# TLS_PWR.net
KiCad netlist of a schematic drawn in Altium Designer
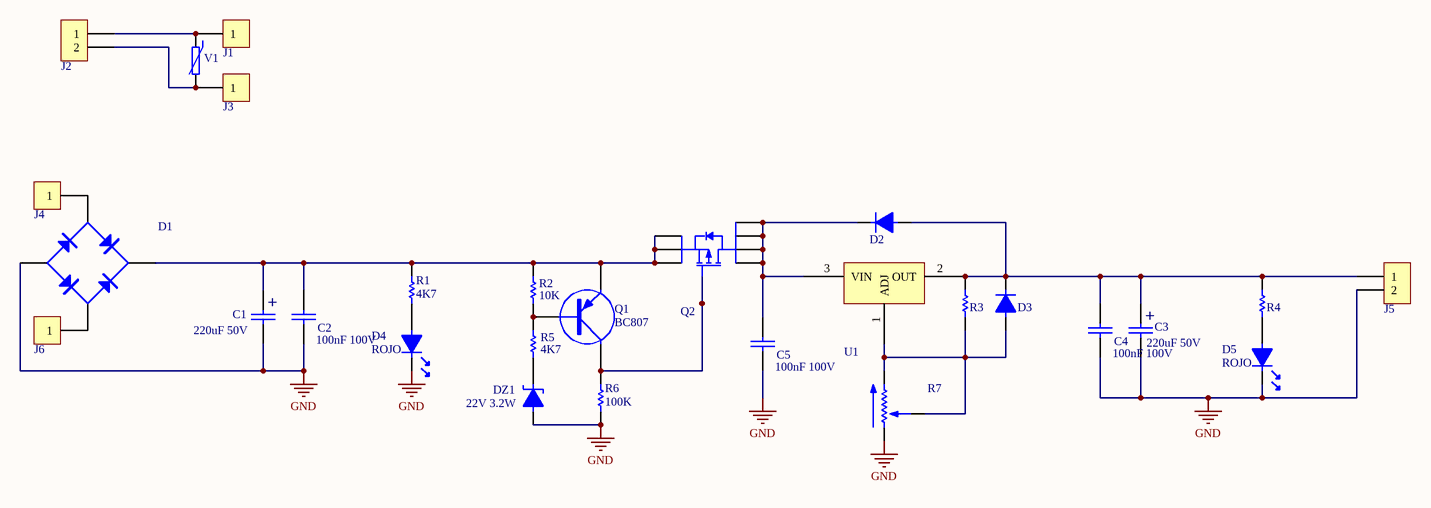
[diagram p0: TLS_PWR.SchDoc]

(export (version "E")
  (design (tool "Eeschema 10.0.6"))
  (components
    (comp (ref "C1")
      (value "220uF 50V")
      (footprint "CAP500RP")
      (description "CAP ELECT 220uF 50V")
      (fields (field (name "PART NUMBER") "CAP_ELECT_220uF_50V") (field (name "MANUFACTURER") "Nichicon"))
      (libsource (lib "gl_LIB") (part "CAPPOL"))
    )
    (comp (ref "C2")
      (value "100nF 100V")
      (footprint "0603")
      (description "CAP0603 100nF 100V X7R")
      (fields (field (name "PART NUMBER") "CAP0603_100nF_100V_X7R") (field (name "MANUFACTURER") "Yageo"))
      (libsource (lib "gl_LIB") (part "CAP"))
    )
    (comp (ref "C3")
      (value "220uF 50V")
      (footprint "CAP500RP")
      (description "CAP ELECT 220uF 50V")
      (fields (field (name "PART NUMBER") "CAP_ELECT_220uF_50V") (field (name "MANUFACTURER") "Nichicon"))
      (libsource (lib "gl_LIB") (part "CAPPOL"))
    )
    (comp (ref "C4")
      (value "100nF 100V")
      (footprint "0603")
      (description "CAP0603 100nF 100V X7R")
      (fields (field (name "PART NUMBER") "CAP0603_100nF_100V_X7R") (field (name "MANUFACTURER") "Yageo"))
      (libsource (lib "gl_LIB") (part "CAP"))
    )
    (comp (ref "C5")
      (value "100nF 100V")
      (footprint "0603")
      (description "CAP0603 100nF 100V X7R")
      (fields (field (name "PART NUMBER") "CAP0603_100nF_100V_X7R") (field (name "MANUFACTURER") "Yageo"))
      (libsource (lib "gl_LIB") (part "CAP"))
    )
    (comp (ref "D1")
      (value "CD-MBL210S")
      (footprint "CD-MBL210S")
      (description "BRIDGE RECT 1PHASE 1KV 2A")
      (fields (field (name "MANUFACTURER") "Bourns Inc."))
      (libsource (lib "gl_LIB") (part "BRIDGE"))
    )
    (comp (ref "D2")
      (value "S1M")
      (footprint "SMAK")
      (description "DIODE GEN PURPOSE 1000V 1A SMAA")
      (fields (field (name "PART NUMBER") "DIO_GEN_PURPOSE_S1M_SMA"))
      (libsource (lib "gl_LIB") (part "DIODO"))
    )
    (comp (ref "D3")
      (value "S1M")
      (footprint "SMAK")
      (description "DIODE GEN PURPOSE 1000V 1A SMAA")
      (fields (field (name "PART NUMBER") "DIO_GEN_PURPOSE_S1M_SMA"))
      (libsource (lib "gl_LIB") (part "DIODO"))
    )
    (comp (ref "D4")
      (value "ROJO")
      (footprint "LED0603_R")
      (description "LED ROJO 0603")
      (fields (field (name "PART NUMBER") "LED0603_ROJO") (field (name "MANUFACTURER") "Lite-On Inc."))
      (libsource (lib "gl_LIB") (part "LED"))
    )
    (comp (ref "D5")
      (value "ROJO")
      (footprint "LED0603_R")
      (description "LED ROJO 0603")
      (fields (field (name "PART NUMBER") "LED0603_ROJO") (field (name "MANUFACTURER") "Lite-On Inc."))
      (libsource (lib "gl_LIB") (part "LED"))
    )
    (comp (ref "DZ1")
      (value "22V 3.2W")
      (footprint "DO-216AA")
      (description "DIODE ZENER 22V 3.2W POWERMITE")
      (fields
        (field (name "PART NUMBER") "DIO_ZEN_22V_DO-216AA")
        (field (name "MANUFACTURER") "ON Semiconductor")
      )
      (libsource (lib "gl_LIB") (part "DIODO ZENER"))
    )
    (comp (ref "J1")
      (value "PIN CABLE")
      (footprint "PIN_CABLE")
      (description "PIN PARA SOLDAR CABLE 1MM")
      (fields (field (name "PART NUMBER") "PIN_1_CABLE_1mm"))
      (libsource (lib "") (part "CON1_TRAMPA_1"))
    )
    (comp (ref "J2")
      (value "BORNERA CON TORNILLO")
      (footprint "BORNERA2")
      (description "BORNERA CON TORNILLO PASO 5mm (2 CONTACTOS)")
      (fields (field (name "PART NUMBER") "BORNERA2_5mm_TORNILLO"))
      (libsource (lib "gl_LIB") (part "CON2"))
    )
    (comp (ref "J3")
      (value "PIN CABLE")
      (footprint "PIN_CABLE")
      (description "PIN PARA SOLDAR CABLE 1MM")
      (fields (field (name "PART NUMBER") "PIN_1_CABLE_1mm"))
      (libsource (lib "") (part "CON1_TRAMPA_1"))
    )
    (comp (ref "J4")
      (value "PIN CABLE")
      (footprint "PIN_CABLE")
      (description "PIN PARA SOLDAR CABLE 1MM")
      (fields (field (name "PART NUMBER") "PIN_1_CABLE_1mm"))
      (libsource (lib "gl_LIB") (part "CON1_TRAMPA"))
    )
    (comp (ref "J5")
      (value "BORNERA CON TORNILLO")
      (footprint "BORNERA2")
      (description "BORNERA CON TORNILLO PASO 5mm (2 CONTACTOS)")
      (fields (field (name "PART NUMBER") "BORNERA2_5mm_TORNILLO"))
      (libsource (lib "") (part "CON2_1"))
    )
    (comp (ref "J6")
      (value "PIN CABLE")
      (footprint "PIN_CABLE")
      (description "PIN PARA SOLDAR CABLE 1MM")
      (fields (field (name "PART NUMBER") "PIN_1_CABLE_1mm"))
      (libsource (lib "gl_LIB") (part "CON1_TRAMPA"))
    )
    (comp (ref "Q1")
      (value "BC807")
      (footprint "SOT23")
      (description "TRANSISTOR PNP 500MA 45V SOT323")
      (fields (field (name "PART NUMBER") "BC807_SOT23"))
      (libsource (lib "gl_LIB") (part "TRANSISTOR PNP"))
    )
    (comp (ref "Q2")
      (value "IRF7240")
      (footprint "SOIC8")
      (description "Fet IRF7240")
      (fields (field (name "PART NUMBER") "IRF7240_SO8"))
      (libsource (lib "gl_LIB") (part "IRF7240"))
    )
    (comp (ref "R1")
      (value "4K7")
      (footprint "0603")
      (description "RES0603 4K7 5%")
      (fields (field (name "PART NUMBER") "RES0603_4K7_5%"))
      (libsource (lib "gl_LIB") (part "RES"))
    )
    (comp (ref "R2")
      (value "10K")
      (footprint "0603")
      (description "RES0603 10K 5%")
      (fields (field (name "PART NUMBER") "RES0603_10K_5%"))
      (libsource (lib "gl_LIB") (part "RES"))
    )
    (comp (ref "R3")
      (value "220R")
      (footprint "0603")
      (description "RES0603 220R 5%")
      (fields (field (name "PART NUMBER") "RES0603_220R_5%"))
      (libsource (lib "gl_LIB") (part "RES"))
    )
    (comp (ref "R4")
      (value "1K")
      (footprint "0603")
      (description "RES0603 1K 5%")
      (fields (field (name "PART NUMBER") "RES0603_1K_5%"))
      (libsource (lib "gl_LIB") (part "RES"))
    )
    (comp (ref "R5")
      (value "4K7")
      (footprint "0603")
      (description "RES0603 4K7 5%")
      (fields (field (name "PART NUMBER") "RES0603_4K7_5%"))
      (libsource (lib "gl_LIB") (part "RES"))
    )
    (comp (ref "R6")
      (value "100K")
      (footprint "0603")
      (description "RES0603 100K 5%")
      (fields (field (name "PART NUMBER") "RES0603_100K_5%"))
      (libsource (lib "gl_LIB") (part "RES"))
    )
    (comp (ref "R7")
      (value "10K")
      (footprint "3296W")
      (description "3296W TRIMMER 10K OHM 0.5W PC PIN")
      (fields (field (name "PART NUMBER") "TRIMMER_3296W_10K") (field (name "MANUFACTURER") "Bourns Inc."))
      (libsource (lib "gl_LIB") (part "RESVAR"))
    )
    (comp (ref "U1")
      (value "LM317")
      (footprint "D2PAK")
      (description "IC REG LIN POS ADJ 1.5A D2PAK-3")
      (fields (field (name "PART NUMBER") "LM317_D2PAK") (field (name "MANUFACTURER") "onsemi"))
      (libsource (lib "gl_LIB") (part "LM317"))
    )
    (comp (ref "V1")
      (value "250V")
      (footprint "VARTH_20")
      (description "VARISTOR 390V 10KA DISC 20MM")
      (fields (field (name "PART NUMBER") "VARTH_250V") (field (name "MANUFACTURER") "TDK Electronics Inc."))
      (libsource (lib "gl_LIB") (part "VARISTOR"))
    )
  )
  (nets
    (net (code "1") (name "GND") (class "Default")
      (node (ref "C1") (pin "2") (pinfunction "2_2") (pintype "passive"))
      (node (ref "C2") (pin "2") (pinfunction "2_2") (pintype "passive"))
      (node (ref "C3") (pin "2") (pinfunction "2_2") (pintype "passive"))
      (node (ref "C4") (pin "2") (pinfunction "2_2") (pintype "passive"))
      (node (ref "C5") (pin "2") (pinfunction "2_2") (pintype "passive"))
      (node (ref "D1") (pin "3") (pinfunction "V-_3") (pintype "passive"))
      (node (ref "D4") (pin "2") (pinfunction "2_2") (pintype "passive"))
      (node (ref "D5") (pin "2") (pinfunction "2_2") (pintype "passive"))
      (node (ref "DZ1") (pin "1") (pinfunction "1_1") (pintype "passive"))
      (node (ref "J5") (pin "2") (pinfunction "2_2") (pintype "passive"))
      (node (ref "R6") (pin "2") (pinfunction "2_2") (pintype "passive"))
      (node (ref "R7") (pin "1") (pinfunction "CCW_1") (pintype "passive"))
    )
    (net (code "2") (name "Net-(D1-AC-Pad2)") (class "Default")
      (node (ref "D1") (pin "2") (pinfunction "AC_2") (pintype "passive"))
      (node (ref "J4") (pin "1") (pinfunction "1_1") (pintype "passive"))
    )
    (net (code "3") (name "Net-(D1-AC-Pad4)") (class "Default")
      (node (ref "D1") (pin "4") (pinfunction "AC_4") (pintype "passive"))
      (node (ref "J6") (pin "1") (pinfunction "1_1") (pintype "passive"))
    )
    (net (code "4") (name "Net-(D1-V+)") (class "Default")
      (node (ref "C1") (pin "1") (pinfunction "1_1") (pintype "passive"))
      (node (ref "C2") (pin "1") (pinfunction "1_1") (pintype "passive"))
      (node (ref "D1") (pin "1") (pinfunction "V+_1") (pintype "passive"))
      (node (ref "Q1") (pin "3") (pinfunction "E_3") (pintype "passive"))
      (node (ref "Q2") (pin "1") (pinfunction "S_1") (pintype "passive"))
      (node (ref "Q2") (pin "2") (pinfunction "S_2") (pintype "passive"))
      (node (ref "Q2") (pin "3") (pinfunction "S_3") (pintype "passive"))
      (node (ref "R1") (pin "2") (pinfunction "2_2") (pintype "passive"))
      (node (ref "R2") (pin "2") (pinfunction "2_2") (pintype "passive"))
    )
    (net (code "5") (name "Net-(D4-Pad1)") (class "Default")
      (node (ref "D4") (pin "1") (pinfunction "1_1") (pintype "passive"))
      (node (ref "R1") (pin "1") (pinfunction "1_1") (pintype "passive"))
    )
    (net (code "6") (name "Net-(D5-Pad1)") (class "Default")
      (node (ref "D5") (pin "1") (pinfunction "1_1") (pintype "passive"))
      (node (ref "R4") (pin "1") (pinfunction "1_1") (pintype "passive"))
    )
    (net (code "7") (name "Net-(DZ1-Pad2)") (class "Default")
      (node (ref "DZ1") (pin "2") (pinfunction "2_2") (pintype "passive"))
      (node (ref "R5") (pin "1") (pinfunction "1_1") (pintype "passive"))
    )
    (net (code "8") (name "Net-(J1-Pad1)") (class "Default")
      (node (ref "J1") (pin "1") (pinfunction "1_1") (pintype "passive"))
      (node (ref "J2") (pin "1") (pinfunction "1_1") (pintype "passive"))
      (node (ref "V1") (pin "1") (pinfunction "1_1") (pintype "passive"))
    )
    (net (code "9") (name "Net-(J2-Pad2)") (class "Default")
      (node (ref "J2") (pin "2") (pinfunction "2_2") (pintype "passive"))
      (node (ref "J3") (pin "1") (pinfunction "1_1") (pintype "passive"))
      (node (ref "V1") (pin "2") (pinfunction "2_2") (pintype "passive"))
    )
    (net (code "10") (name "Net-(Q1-B)") (class "Default")
      (node (ref "Q1") (pin "1") (pinfunction "B_1") (pintype "passive"))
      (node (ref "R2") (pin "1") (pinfunction "1_1") (pintype "passive"))
      (node (ref "R5") (pin "2") (pinfunction "2_2") (pintype "passive"))
    )
    (net (code "11") (name "Net-(Q1-C)") (class "Default")
      (node (ref "Q1") (pin "2") (pinfunction "C_2") (pintype "passive"))
      (node (ref "Q2") (pin "4") (pinfunction "G_4") (pintype "passive"))
      (node (ref "R6") (pin "1") (pinfunction "1_1") (pintype "passive"))
    )
    (net (code "12") (name "Net-(R7-CW)") (class "Default")
      (node (ref "D3") (pin "1") (pinfunction "1_1") (pintype "passive"))
      (node (ref "R3") (pin "1") (pinfunction "1_1") (pintype "passive"))
      (node (ref "R7") (pin "2") (pinfunction "WIPER_2") (pintype "passive"))
      (node (ref "R7") (pin "3") (pinfunction "CW_3") (pintype "passive"))
      (node (ref "U1") (pin "1") (pinfunction "ADJ_1") (pintype "passive"))
    )
    (net (code "13") (name "Net-(U1-OUT)") (class "Default")
      (node (ref "C3") (pin "1") (pinfunction "1_1") (pintype "passive"))
      (node (ref "C4") (pin "1") (pinfunction "1_1") (pintype "passive"))
      (node (ref "D2") (pin "1") (pinfunction "1_1") (pintype "passive"))
      (node (ref "D3") (pin "2") (pinfunction "2_2") (pintype "passive"))
      (node (ref "J5") (pin "1") (pinfunction "1_1") (pintype "passive"))
      (node (ref "R3") (pin "2") (pinfunction "2_2") (pintype "passive"))
      (node (ref "R4") (pin "2") (pinfunction "2_2") (pintype "passive"))
      (node (ref "U1") (pin "2") (pinfunction "OUT_2") (pintype "passive"))
    )
    (net (code "14") (name "Net-(U1-VIN)") (class "Default")
      (node (ref "C5") (pin "1") (pinfunction "1_1") (pintype "passive"))
      (node (ref "D2") (pin "2") (pinfunction "2_2") (pintype "passive"))
      (node (ref "Q2") (pin "5") (pinfunction "D_5") (pintype "passive"))
      (node (ref "Q2") (pin "6") (pinfunction "D_6") (pintype "passive"))
      (node (ref "Q2") (pin "7") (pinfunction "D_7") (pintype "passive"))
      (node (ref "Q2") (pin "8") (pinfunction "D_8") (pintype "passive"))
      (node (ref "U1") (pin "3") (pinfunction "VIN_3") (pintype "passive"))
    )
  )
)
